# RC_RX_CABELL_V3_FHSS_No_Diversity_No_SBU.net
KiCad netlist of a schematic drawn in EAGLE
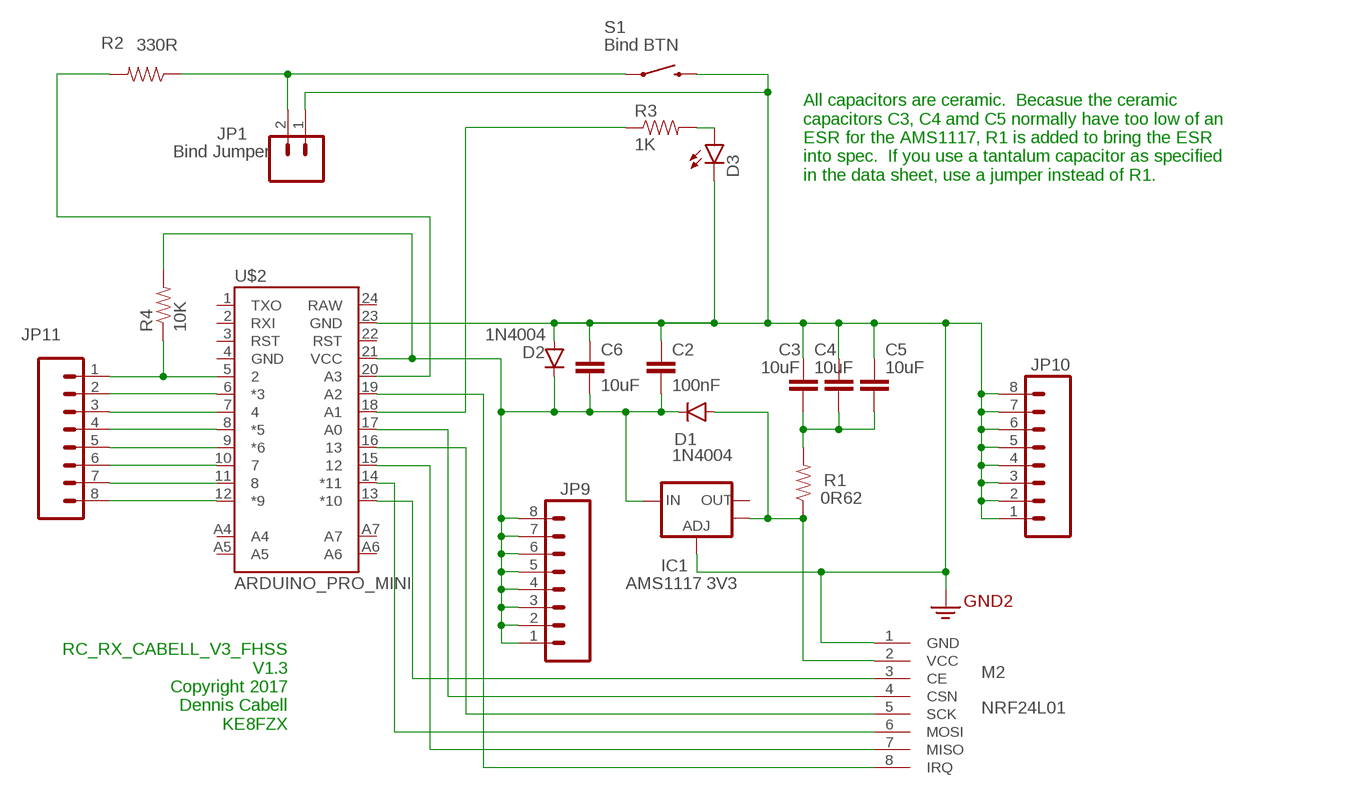
[diagram p0: schematic, sheet 1]

(export (version "E")
  (design (tool "Eeschema 10.0.6"))
  (components
    (comp (ref "C2")
      (value "100nF")
      (footprint "eagle-import:CAP-PTH-5MM")
      (libsource (lib "eagle-import") (part "CAPPTH1"))
    )
    (comp (ref "C3")
      (value "10uF")
      (footprint "eagle-import:CAP-PTH-5MM")
      (libsource (lib "eagle-import") (part "CAPPTH1"))
    )
    (comp (ref "C4")
      (value "10uF")
      (footprint "eagle-import:CAP-PTH-5MM")
      (libsource (lib "eagle-import") (part "CAPPTH1"))
    )
    (comp (ref "C5")
      (value "10uF")
      (footprint "eagle-import:CAP-PTH-5MM")
      (libsource (lib "eagle-import") (part "CAPPTH1"))
    )
    (comp (ref "C6")
      (value "10uF")
      (footprint "eagle-import:CAP-PTH-5MM")
      (libsource (lib "eagle-import") (part "CAPPTH1"))
    )
    (comp (ref "D1")
      (value "1N4004")
      (footprint "eagle-import:DIODE-1N4001")
      (libsource (lib "eagle-import") (part "DIODEPTH"))
    )
    (comp (ref "D2")
      (value "1N4004")
      (footprint "eagle-import:DIODE-1N4001")
      (libsource (lib "eagle-import") (part "DIODEPTH"))
    )
    (comp (ref "D3")
      (value "LED3MM")
      (footprint "eagle-import:LED3MM")
      (libsource (lib "eagle-import") (part "LED3MM"))
    )
    (comp (ref "IC1")
      (value "AMS1117 3V3")
      (footprint "eagle-import:SOT223")
      (libsource (lib "eagle-import") (part "V_REG_LM1117SOT223"))
    )
    (comp (ref "JP1")
      (value "Bind Jumper")
      (footprint "eagle-import:1X02")
      (libsource (lib "eagle-import") (part "M02PTH"))
    )
    (comp (ref "JP9")
      (value "M08")
      (footprint "eagle-import:1X08_ROUND")
      (libsource (lib "eagle-import") (part "M08"))
    )
    (comp (ref "JP10")
      (value "M08")
      (footprint "eagle-import:1X08_ROUND")
      (libsource (lib "eagle-import") (part "M08"))
    )
    (comp (ref "JP11")
      (value "M08")
      (footprint "eagle-import:1X08_ROUND")
      (libsource (lib "eagle-import") (part "M08"))
    )
    (comp (ref "M2")
      (value "NRF24L01")
      (footprint "eagle-import:WIRELESS-NRF24L01")
      (libsource (lib "eagle-import") (part "WIRELESS-NRF24L01"))
    )
    (comp (ref "R1")
      (value "0R62")
      (footprint "eagle-import:AXIAL-0.5")
      (libsource (lib "eagle-import") (part "RESISTORPTH-1/2W"))
    )
    (comp (ref "R2")
      (value "330R")
      (footprint "eagle-import:AXIAL-0.3")
      (libsource (lib "eagle-import") (part "RESISTORAXIAL-0.3"))
    )
    (comp (ref "R3")
      (value "1K")
      (footprint "eagle-import:AXIAL-0.3")
      (libsource (lib "eagle-import") (part "RESISTORAXIAL-0.3"))
    )
    (comp (ref "R4")
      (value "10K")
      (footprint "eagle-import:AXIAL-0.3")
      (libsource (lib "eagle-import") (part "RESISTORAXIAL-0.3"))
    )
    (comp (ref "S1")
      (value "Bind BTN")
      (footprint "eagle-import:TACTILE-SWITCH-1101NE")
      (libsource (lib "eagle-import") (part "SWITCH-MOMENTARY-2SMD-1101NE"))
    )
    (comp (ref "U$2")
      (value "ARDUINO_PRO_MINI")
      (footprint "eagle-import:ARDUINO_PRO_MINI")
      (libsource (lib "eagle-import") (part "ARDUINO_PRO_MINI"))
    )
  )
  (nets
    (net (code "1") (name "GND2") (class "Default")
      (node (ref "C2") (pin "1") (pinfunction "1_1") (pintype "passive"))
      (node (ref "C3") (pin "1") (pinfunction "1_1") (pintype "passive"))
      (node (ref "C4") (pin "1") (pinfunction "1_1") (pintype "passive"))
      (node (ref "C5") (pin "1") (pinfunction "1_1") (pintype "passive"))
      (node (ref "C6") (pin "1") (pinfunction "1_1") (pintype "passive"))
      (node (ref "D2") (pin "A") (pinfunction "A_A") (pintype "passive"))
      (node (ref "D3") (pin "K") (pinfunction "C_K") (pintype "passive"))
      (node (ref "IC1") (pin "1") (pinfunction "ADJ_1") (pintype "input"))
      (node (ref "JP1") (pin "1") (pinfunction "1_1") (pintype "passive"))
      (node (ref "JP10") (pin "1") (pinfunction "1_1") (pintype "passive"))
      (node (ref "JP10") (pin "2") (pinfunction "2_2") (pintype "passive"))
      (node (ref "JP10") (pin "3") (pinfunction "3_3") (pintype "passive"))
      (node (ref "JP10") (pin "4") (pinfunction "4_4") (pintype "passive"))
      (node (ref "JP10") (pin "5") (pinfunction "5_5") (pintype "passive"))
      (node (ref "JP10") (pin "6") (pinfunction "6_6") (pintype "passive"))
      (node (ref "JP10") (pin "7") (pinfunction "7_7") (pintype "passive"))
      (node (ref "JP10") (pin "8") (pinfunction "8_8") (pintype "passive"))
      (node (ref "M2") (pin "1") (pinfunction "GND_1") (pintype "power_in"))
      (node (ref "S1") (pin "2") (pinfunction "2_2") (pintype "passive"))
      (node (ref "U$2") (pin "23") (pinfunction "GND_23") (pintype "bidirectional"))
    )
    (net (code "2") (name "Net-(IC1-IN)") (class "Default")
      (node (ref "C2") (pin "2") (pinfunction "2_2") (pintype "passive"))
      (node (ref "C6") (pin "2") (pinfunction "2_2") (pintype "passive"))
      (node (ref "D1") (pin "C") (pinfunction "C_C") (pintype "passive"))
      (node (ref "D2") (pin "C") (pinfunction "C_C") (pintype "passive"))
      (node (ref "IC1") (pin "3") (pinfunction "IN_3") (pintype "input"))
      (node (ref "JP9") (pin "1") (pinfunction "1_1") (pintype "passive"))
      (node (ref "JP9") (pin "2") (pinfunction "2_2") (pintype "passive"))
      (node (ref "JP9") (pin "3") (pinfunction "3_3") (pintype "passive"))
      (node (ref "JP9") (pin "4") (pinfunction "4_4") (pintype "passive"))
      (node (ref "JP9") (pin "5") (pinfunction "5_5") (pintype "passive"))
      (node (ref "JP9") (pin "6") (pinfunction "6_6") (pintype "passive"))
      (node (ref "JP9") (pin "7") (pinfunction "7_7") (pintype "passive"))
      (node (ref "JP9") (pin "8") (pinfunction "8_8") (pintype "passive"))
      (node (ref "R4") (pin "P$2") (pinfunction "2_P$2") (pintype "passive"))
      (node (ref "U$2") (pin "21") (pinfunction "VCC_21") (pintype "bidirectional"))
    )
    (net (code "3") (name "Net-(M2-CE)") (class "Default")
      (node (ref "M2") (pin "3") (pinfunction "CE_3") (pintype "bidirectional"))
      (node (ref "U$2") (pin "13") (pinfunction "*10_13") (pintype "bidirectional"))
    )
    (net (code "4") (name "Net-(M2-CSN)") (class "Default")
      (node (ref "M2") (pin "4") (pinfunction "CSN_4") (pintype "bidirectional"))
      (node (ref "U$2") (pin "17") (pinfunction "A0_17") (pintype "bidirectional"))
    )
    (net (code "5") (name "Net-(M2-IRQ)") (class "Default")
      (node (ref "M2") (pin "8") (pinfunction "IRQ_8") (pintype "bidirectional"))
      (node (ref "U$2") (pin "19") (pinfunction "A2_19") (pintype "bidirectional"))
    )
    (net (code "6") (name "Net-(M2-MISO)") (class "Default")
      (node (ref "M2") (pin "7") (pinfunction "MISO_7") (pintype "bidirectional"))
      (node (ref "U$2") (pin "15") (pinfunction "12_15") (pintype "bidirectional"))
    )
    (net (code "7") (name "Net-(M2-MOSI)") (class "Default")
      (node (ref "M2") (pin "6") (pinfunction "MOSI_6") (pintype "bidirectional"))
      (node (ref "U$2") (pin "14") (pinfunction "*11_14") (pintype "bidirectional"))
    )
    (net (code "8") (name "Net-(M2-SCK)") (class "Default")
      (node (ref "M2") (pin "5") (pinfunction "SCK_5") (pintype "bidirectional"))
      (node (ref "U$2") (pin "16") (pinfunction "13_16") (pintype "bidirectional"))
    )
    (net (code "9") (name "Net-(M2-VCC)") (class "Default")
      (node (ref "D1") (pin "A") (pinfunction "A_A") (pintype "passive"))
      (node (ref "IC1") (pin "4") (pinfunction "OUT_4") (pintype "output"))
      (node (ref "M2") (pin "2") (pinfunction "VCC_2") (pintype "power_in"))
      (node (ref "R1") (pin "P$1") (pinfunction "1_P$1") (pintype "passive"))
    )
    (net (code "10") (name "Net-(R1-2)") (class "Default")
      (node (ref "C3") (pin "2") (pinfunction "2_2") (pintype "passive"))
      (node (ref "C4") (pin "2") (pinfunction "2_2") (pintype "passive"))
      (node (ref "C5") (pin "2") (pinfunction "2_2") (pintype "passive"))
      (node (ref "R1") (pin "P$2") (pinfunction "2_P$2") (pintype "passive"))
    )
    (net (code "11") (name "Net-(R2-1)") (class "Default")
      (node (ref "JP1") (pin "2") (pinfunction "2_2") (pintype "passive"))
      (node (ref "R2") (pin "P$1") (pinfunction "1_P$1") (pintype "passive"))
      (node (ref "S1") (pin "1") (pinfunction "1_1") (pintype "passive"))
    )
    (net (code "12") (name "Net-(R2-2)") (class "Default")
      (node (ref "R2") (pin "P$2") (pinfunction "2_P$2") (pintype "passive"))
      (node (ref "U$2") (pin "20") (pinfunction "A3_20") (pintype "bidirectional"))
    )
    (net (code "13") (name "Net-(R3-1)") (class "Default")
      (node (ref "R3") (pin "P$1") (pinfunction "1_P$1") (pintype "passive"))
      (node (ref "U$2") (pin "18") (pinfunction "A1_18") (pintype "bidirectional"))
    )
    (net (code "14") (name "Net-(R3-2)") (class "Default")
      (node (ref "D3") (pin "A") (pinfunction "A_A") (pintype "passive"))
      (node (ref "R3") (pin "P$2") (pinfunction "2_P$2") (pintype "passive"))
    )
    (net (code "15") (name "Net-(R4-1)") (class "Default")
      (node (ref "JP11") (pin "1") (pinfunction "1_1") (pintype "passive"))
      (node (ref "R4") (pin "P$1") (pinfunction "1_P$1") (pintype "passive"))
      (node (ref "U$2") (pin "5") (pinfunction "2_5") (pintype "bidirectional"))
    )
    (net (code "16") (name "Net-(U$2-*3)") (class "Default")
      (node (ref "JP11") (pin "2") (pinfunction "2_2") (pintype "passive"))
      (node (ref "U$2") (pin "6") (pinfunction "*3_6") (pintype "bidirectional"))
    )
    (net (code "17") (name "Net-(U$2-*5)") (class "Default")
      (node (ref "JP11") (pin "4") (pinfunction "4_4") (pintype "passive"))
      (node (ref "U$2") (pin "8") (pinfunction "*5_8") (pintype "bidirectional"))
    )
    (net (code "18") (name "Net-(U$2-*6)") (class "Default")
      (node (ref "JP11") (pin "5") (pinfunction "5_5") (pintype "passive"))
      (node (ref "U$2") (pin "9") (pinfunction "*6_9") (pintype "bidirectional"))
    )
    (net (code "19") (name "Net-(U$2-*9)") (class "Default")
      (node (ref "JP11") (pin "8") (pinfunction "8_8") (pintype "passive"))
      (node (ref "U$2") (pin "12") (pinfunction "*9_12") (pintype "bidirectional"))
    )
    (net (code "20") (name "Net-(U$2-4)") (class "Default")
      (node (ref "JP11") (pin "3") (pinfunction "3_3") (pintype "passive"))
      (node (ref "U$2") (pin "7") (pinfunction "4_7") (pintype "bidirectional"))
    )
    (net (code "21") (name "Net-(U$2-7)") (class "Default")
      (node (ref "JP11") (pin "6") (pinfunction "6_6") (pintype "passive"))
      (node (ref "U$2") (pin "10") (pinfunction "7_10") (pintype "bidirectional"))
    )
    (net (code "22") (name "Net-(U$2-8)") (class "Default")
      (node (ref "JP11") (pin "7") (pinfunction "7_7") (pintype "passive"))
      (node (ref "U$2") (pin "11") (pinfunction "8_11") (pintype "bidirectional"))
    )
    (net (code "23") (name "unconnected-(IC1-OUT-Pad2)") (class "Default")
      (node (ref "IC1") (pin "2") (pinfunction "OUT_2") (pintype "output"))
    )
    (net (code "24") (name "unconnected-(U$2-GND-Pad4)") (class "Default")
      (node (ref "U$2") (pin "4") (pinfunction "GND_4") (pintype "bidirectional"))
    )
    (net (code "25") (name "unconnected-(U$2-PadA4)") (class "Default")
      (node (ref "U$2") (pin "A4") (pinfunction "A4_A4") (pintype "bidirectional"))
    )
    (net (code "26") (name "unconnected-(U$2-PadA5)") (class "Default")
      (node (ref "U$2") (pin "A5") (pinfunction "A5_A5") (pintype "bidirectional"))
    )
    (net (code "27") (name "unconnected-(U$2-PadA6)") (class "Default")
      (node (ref "U$2") (pin "A6") (pinfunction "A6_A6") (pintype "bidirectional"))
    )
    (net (code "28") (name "unconnected-(U$2-PadA7)") (class "Default")
      (node (ref "U$2") (pin "A7") (pinfunction "A7_A7") (pintype "bidirectional"))
    )
    (net (code "29") (name "unconnected-(U$2-RAW-Pad24)") (class "Default")
      (node (ref "U$2") (pin "24") (pinfunction "RAW_24") (pintype "bidirectional"))
    )
    (net (code "30") (name "unconnected-(U$2-RST-Pad3)") (class "Default")
      (node (ref "U$2") (pin "3") (pinfunction "RST_3") (pintype "bidirectional"))
    )
    (net (code "31") (name "unconnected-(U$2-RST-Pad22)") (class "Default")
      (node (ref "U$2") (pin "22") (pinfunction "RST_22") (pintype "bidirectional"))
    )
    (net (code "32") (name "unconnected-(U$2-RXI-Pad2)") (class "Default")
      (node (ref "U$2") (pin "2") (pinfunction "RXI_2") (pintype "bidirectional"))
    )
    (net (code "33") (name "unconnected-(U$2-TXO-Pad1)") (class "Default")
      (node (ref "U$2") (pin "1") (pinfunction "TXO_1") (pintype "bidirectional"))
    )
  )
)
